# led_buttons-1.net
KiCad netlist of a schematic drawn in EAGLE
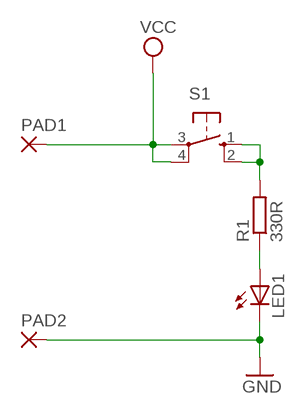
[diagram p0: schematic, sheet 1]

(export (version "E")
  (design (tool "Eeschema 10.0.6"))
  (components
    (comp (ref "LED1")
      (value "LEDCHIP-LED0603")
      (footprint "eagle-import:CHIP-LED0603")
      (libsource (lib "eagle-import") (part "LEDCHIP-LED0603"))
    )
    (comp (ref "PAD1")
      (value "SMD5")
      (footprint "eagle-import:SMD2,54-5,08")
      (libsource (lib "eagle-import") (part "SMD5"))
    )
    (comp (ref "PAD2")
      (value "SMD5")
      (footprint "eagle-import:SMD2,54-5,08")
      (libsource (lib "eagle-import") (part "SMD5"))
    )
    (comp (ref "R1")
      (value "330R")
      (footprint "eagle-import:R0603")
      (libsource (lib "eagle-import") (part "R-EU_R0603"))
    )
    (comp (ref "S1")
      (value "10-XX")
      (footprint "eagle-import:B3F-10XX")
      (fields (field (name "MPN") "B3F-1000"))
      (libsource (lib "eagle-import") (part "10-XX"))
    )
  )
  (nets
    (net (code "1") (name "GND") (class "Default")
      (node (ref "LED1") (pin "C") (pinfunction "C_C") (pintype "passive"))
      (node (ref "PAD2") (pin "1") (pinfunction "P_1") (pintype "passive"))
    )
    (net (code "2") (name "Net-(LED1-PadA)") (class "Default")
      (node (ref "LED1") (pin "A") (pinfunction "A_A") (pintype "passive"))
      (node (ref "R1") (pin "1") (pinfunction "1_1") (pintype "passive"))
    )
    (net (code "3") (name "Net-(S1-S)") (class "Default")
      (node (ref "R1") (pin "2") (pinfunction "2_2") (pintype "passive"))
      (node (ref "S1") (pin "1") (pinfunction "S_1") (pintype "passive"))
      (node (ref "S1") (pin "2") (pinfunction "S1_2") (pintype "passive"))
    )
    (net (code "4") (name "VCC") (class "Default")
      (node (ref "PAD1") (pin "1") (pinfunction "P_1") (pintype "passive"))
      (node (ref "S1") (pin "3") (pinfunction "P_3") (pintype "passive"))
      (node (ref "S1") (pin "4") (pinfunction "P1_4") (pintype "passive"))
    )
  )
)
